# POE_Sheet.net
KiCad netlist of a schematic drawn in Altium Designer
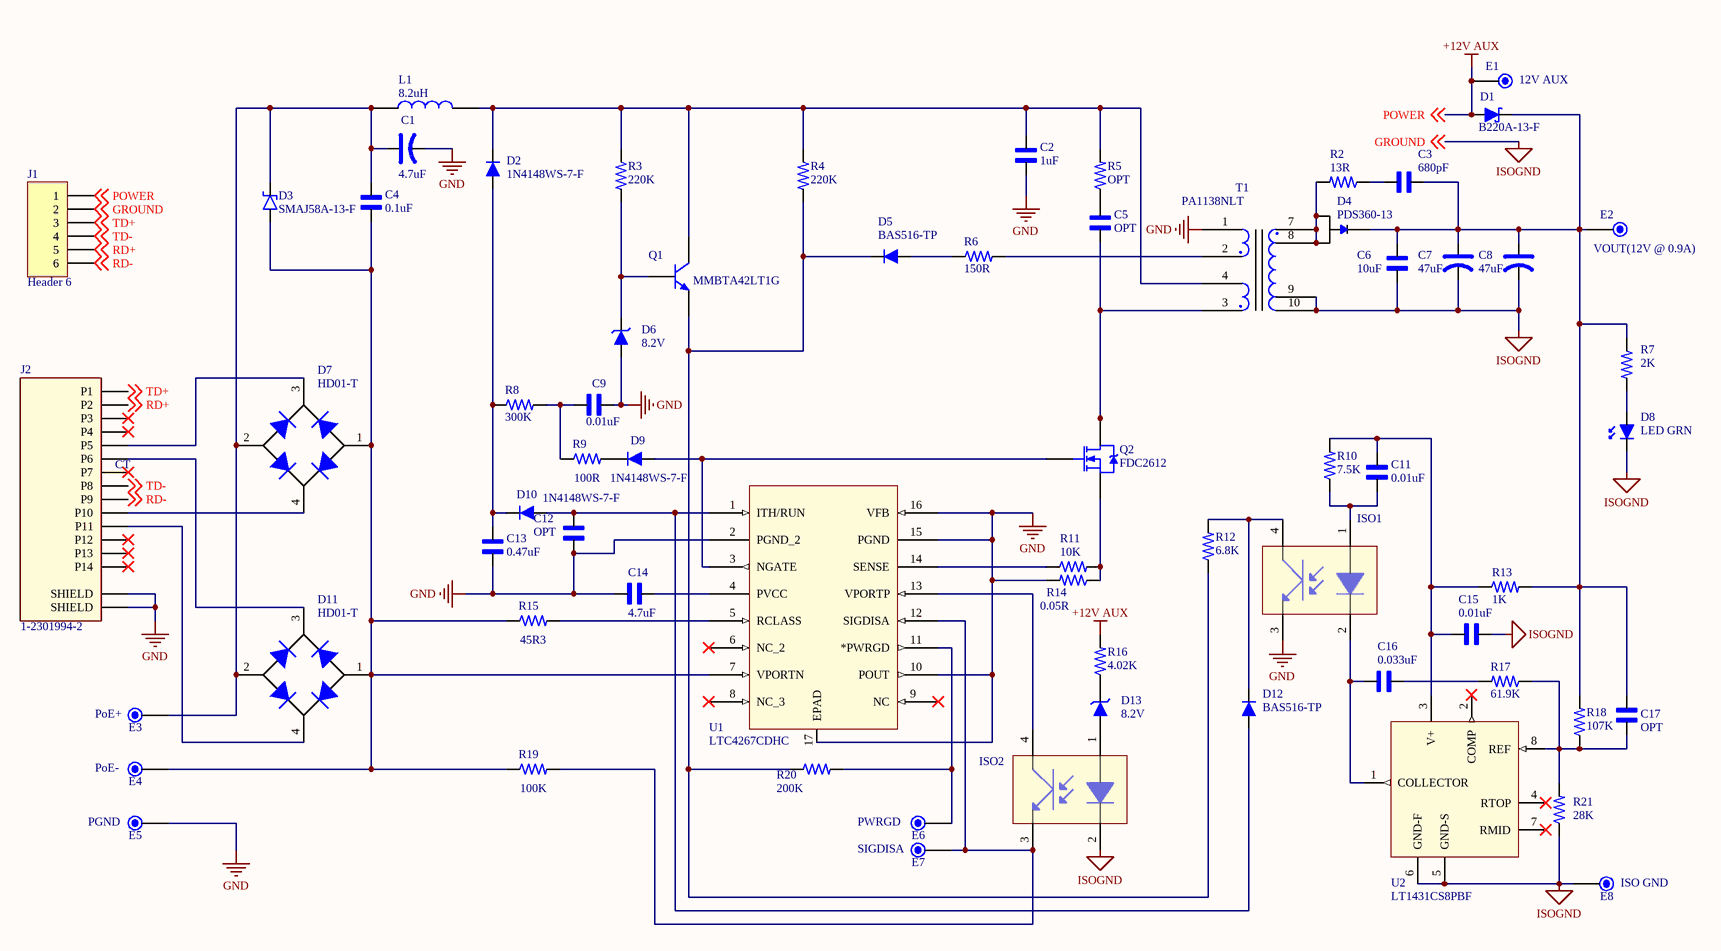
[diagram p0: POE_Sheet.SchDoc]

(export (version "E")
  (design (tool "Eeschema 10.0.6"))
  (components
    (comp (ref "C1")
      (value "4.7uF")
      (footprint "CAPAE5953X52M")
      (description "4.7µF 63V Aluminum Electrolytic Capacitors Radial, Can - SMD 2000 Hrs @ 85°C")
      (fields (field (name "MF") "United Chemi-Con") (field (name "MP") "EMVA630ADA4R7ME55G"))
      (libsource (lib "POE_Schlib") (part "EMVA630ADA4R7ME55G"))
    )
    (comp (ref "C2")
      (value "1uF")
      (footprint "*CAPC1005X55N")
      (description "1µF ±10% 6.3V Ceramic Capacitor X6S 0402 (1005 Metric)")
      (fields (field (name "MF") "Taiyo Yuden") (field (name "MP") "JMK105C6105KV-F"))
      (libsource (lib "POE_Schlib") (part "JMK105C6105KV-F"))
    )
    (comp (ref "C3")
      (value "680pF")
      (footprint "*CAPC1005X55N")
      (description "680pF ±10% 50V Ceramic Capacitor X7R 0402 (1005 Metric)")
      (fields (field (name "MF") "Yageo") (field (name "MP") "CC0402KRX7R9BB681"))
      (libsource (lib "POE_Schlib") (part "CC0402KRX7R9BB681"))
    )
    (comp (ref "C4")
      (value "0.1uF")
      (footprint "*CAPC1005X55N")
      (description "SMD Capacitor X7R(EIA) with Capacitance: 0.10uF Tol. 10%. Rated Voltage: 50Vdc")
      (fields (field (name "MF") "Murata Electronics") (field (name "MP") "GRM155R71H104KE14J"))
      (libsource (lib "POE_Schlib") (part "GRM155R71H104KE14J"))
    )
    (comp (ref "C5") (value "OPT") (footprint "*CAPC1005X55N") (libsource (lib "POE_Schlib") (part "OPT_C")))
    (comp (ref "C6")
      (value "10uF")
      (footprint "*CAPC1005X55N")
      (description "10µF ±20% 4V Ceramic Capacitor X5R 0402 (1005 Metric)")
      (fields (field (name "MF") "Murata Electronics") (field (name "MP") "GRM155R60G106ME44D"))
      (libsource (lib "POE_Schlib") (part "GRM155R60G106ME44D"))
    )
    (comp (ref "C7")
      (value "47uF")
      (footprint "CAPM6032X22N")
      (description "47µF Molded Tantalum Capacitors 16V 2312 (6032 Metric) 350mOhm")
      (fields (field (name "MF") "AVX Corporation") (field (name "MP") "TPSC476K016R0350"))
      (libsource (lib "POE_Schlib") (part "TPSC476K016R0350"))
    )
    (comp (ref "C8")
      (value "47uF")
      (footprint "CAPM6032X22N")
      (description "47µF Molded Tantalum Capacitors 16V 2312 (6032 Metric) 350mOhm")
      (fields (field (name "MF") "AVX Corporation") (field (name "MP") "TPSC476K016R0350"))
      (libsource (lib "POE_Schlib") (part "TPSC476K016R0350"))
    )
    (comp (ref "C9")
      (value "0.01uF")
      (footprint "*CAPC1005X55N")
      (description "0.01uF ±10% 25V Ceramic Capacitor X5R 0402 (1005 Metric)")
      (fields (field (name "MF") "Murata Electronics") (field (name "MP") "GRM155R61E103KA01D"))
      (libsource (lib "POE_Schlib") (part "GRM155R61E103KA01D"))
    )
    (comp (ref "C11")
      (value "0.01uF")
      (footprint "*CAPC1005X55N")
      (description "0.01uF ±10% 25V Ceramic Capacitor X5R 0402 (1005 Metric)")
      (fields (field (name "MF") "Murata Electronics") (field (name "MP") "GRM155R61E103KA01D"))
      (libsource (lib "POE_Schlib") (part "GRM155R61E103KA01D"))
    )
    (comp (ref "C12") (value "OPT") (footprint "*CAPC1005X55N") (libsource (lib "POE_Schlib") (part "OPT_C")))
    (comp (ref "C13")
      (value "0.47uF")
      (footprint "*CAPC1005X55N")
      (description "0.47µF ±10% 50V Ceramic Capacitor X5R 0402 (1005 Metric)")
      (fields (field (name "MF") "Murata Electronics") (field (name "MP") "GRM155R61H474KE11D"))
      (libsource (lib "POE_Schlib") (part "GRM155R61H474KE11D"))
    )
    (comp (ref "C14")
      (value "4.7uF")
      (footprint "*CAPC1005X55N")
      (description "4.7µF ±20% 6.3V Ceramic Capacitor X5R 0402 (1005 Metric)")
      (fields (field (name "MF") "Murata Electronics") (field (name "MP") "GRM155R60J475ME47D"))
      (libsource (lib "POE_Schlib") (part "GRM155R60J475ME47D"))
    )
    (comp (ref "C15")
      (value "0.01uF")
      (footprint "*CAPC1005X55N")
      (description "0.01uF ±10% 25V Ceramic Capacitor X5R 0402 (1005 Metric)")
      (fields (field (name "MF") "Murata Electronics") (field (name "MP") "GRM155R61E103KA01D"))
      (libsource (lib "POE_Schlib") (part "GRM155R61E103KA01D"))
    )
    (comp (ref "C16")
      (value "0.033uF")
      (footprint "*CAPC1005X55N")
      (description "0.033µF -20%, +80% 16V Ceramic Capacitor Y5V (F) 0402 (1005 Metric)")
      (fields (field (name "MF") "Yageo") (field (name "MP") "CC0402ZRY5V7BB333"))
      (libsource (lib "POE_Schlib") (part "CC0402ZRY5V7BB333"))
    )
    (comp (ref "C17") (value "OPT") (footprint "*CAPC1005X55N") (libsource (lib "POE_Schlib") (part "OPT_C")))
    (comp (ref "D1")
      (value "B220A-13-F")
      (footprint "*SMA-DIODE")
      (description "Diode Schottky 20V 2A Surface Mount SMA")
      (fields
        (field (name "DIGI-KEY PART NUMBER") "B220A-FDITR-ND")
        (field (name "MF") "Diodes Incorporated")
      )
      (libsource (lib "POE_Schlib") (part "B220A-13-F"))
    )
    (comp (ref "D2")
      (value "1N4148WS-7-F")
      (footprint "*SOD323_1N4148WS-7-F(Primary)")
      (description "Diode Standard 75V 150mA Surface Mount SOD-323")
      (fields
        (field (name "DIGI-KEY PART NUMBER") "1N4148WS-FDITR-ND")
        (field (name "MF") "Diodes Incorporated")
      )
      (libsource (lib "POE_Schlib") (part "1N4148WS-7-F"))
    )
    (comp (ref "D3")
      (value "SMAJ58A-13-F")
      (footprint "POE_PcbLib:SMAJ")
      (description "93.6V Clamp 4.3A Ipp Tvs Diode Surface Mount SMA")
      (fields (field (name "MF") "Littelfuse Inc."))
      (libsource (lib "POE_Schlib") (part "SMAJ58A-13-F"))
    )
    (comp (ref "D4")
      (value "PDS360-13")
      (footprint "*DIO_PDS360-13")
      (libsource (lib "POE_Schlib") (part "PDS360-13"))
    )
    (comp (ref "D5")
      (value "BAS516-TP")
      (footprint "*SOD323_1N4148WS-7-F(Primary)")
      (description "Diode Standard 75V 250mA (DC) Surface Mount SOD-523")
      (fields
        (field (name "DIGI-KEY PART NUMBER") "BAS516-TPMSTR-ND")
        (field (name "MF") "Micro Commercial Co")
      )
      (libsource (lib "POE_Schlib") (part "BAS516-TP"))
    )
    (comp (ref "D6")
      (value "8.2V")
      (footprint "*SOD323_1N4148WS-7-F(Primary)")
      (description "Zener Diode 8.2V 300mW ±2% Surface Mount SOD-323")
      (fields
        (field (name "DIGI-KEY_PART_NUMBER") "MM3Z8V2ST1GOSTR-ND")
        (field (name "MF") "ON Semiconductor")
      )
      (libsource (lib "POE_Schlib") (part "MM3Z8V2ST1G"))
    )
    (comp (ref "D7")
      (value "HD01-T")
      (footprint "HD01-T")
      (description "Bridge Rectifier Single Phase Standard 100V Surface Mount 4-MiniDIP")
      (fields (field (name "MF") "Diodes Incorporated"))
      (libsource (lib "POE_Schlib") (part "HD01-T"))
    )
    (comp (ref "D8")
      (value "LED GRN")
      (footprint "POE_PcbLib:LED1210")
      (description "Green 525nm LED Indication - Discrete 3.3V 1210 (3225 Metric)")
      (fields (field (name "MP") "APD3224ZGC-F01") (field (name "DIGI-KEY_PART_NUMBER") "754-1089-2-ND"))
      (libsource (lib "POE_Schlib") (part "APD3224ZGC-F01"))
    )
    (comp (ref "D9")
      (value "1N4148WS-7-F")
      (footprint "*SOD323_1N4148WS-7-F(Primary)")
      (description "Diode Standard 75V 150mA Surface Mount SOD-323")
      (fields
        (field (name "DIGI-KEY PART NUMBER") "1N4148WS-FDITR-ND")
        (field (name "MF") "Diodes Incorporated")
      )
      (libsource (lib "POE_Schlib") (part "1N4148WS-7-F"))
    )
    (comp (ref "D10")
      (value "1N4148WS-7-F")
      (footprint "*SOD323_1N4148WS-7-F(Primary)")
      (description "Diode Standard 75V 150mA Surface Mount SOD-323")
      (fields
        (field (name "DIGI-KEY PART NUMBER") "1N4148WS-FDITR-ND")
        (field (name "MF") "Diodes Incorporated")
      )
      (libsource (lib "POE_Schlib") (part "1N4148WS-7-F"))
    )
    (comp (ref "D11")
      (value "HD01-T")
      (footprint "HD01-T")
      (description "Bridge Rectifier Single Phase Standard 100V Surface Mount 4-MiniDIP")
      (fields (field (name "MF") "Diodes Incorporated"))
      (libsource (lib "POE_Schlib") (part "HD01-T"))
    )
    (comp (ref "D12")
      (value "BAS516-TP")
      (footprint "*SOD323_1N4148WS-7-F(Primary)")
      (description "Diode Standard 75V 250mA (DC) Surface Mount SOD-523")
      (fields
        (field (name "DIGI-KEY PART NUMBER") "BAS516-TPMSTR-ND")
        (field (name "MF") "Micro Commercial Co")
      )
      (libsource (lib "POE_Schlib") (part "BAS516-TP"))
    )
    (comp (ref "D13")
      (value "8.2V")
      (footprint "*SOD323_1N4148WS-7-F(Primary)")
      (description "Zener Diode 8.2V 300mW ±2% Surface Mount SOD-323")
      (fields
        (field (name "DIGI-KEY_PART_NUMBER") "MM3Z8V2ST1GOSTR-ND")
        (field (name "MF") "ON Semiconductor")
      )
      (libsource (lib "POE_Schlib") (part "MM3Z8V2ST1G"))
    )
    (comp (ref "E1") (value "12V AUX") (footprint "E_PAD") (libsource (lib "POE_Schlib") (part "E_PAD")))
    (comp (ref "E2")
      (value "VOUT(12V @ 0.9A)")
      (footprint "E_PAD")
      (libsource (lib "POE_Schlib") (part "E_PAD"))
    )
    (comp (ref "E3") (value "PoE+") (footprint "E_PAD") (libsource (lib "POE_Schlib") (part "E_PAD")))
    (comp (ref "E4") (value "PoE-") (footprint "E_PAD") (libsource (lib "POE_Schlib") (part "E_PAD")))
    (comp (ref "E5") (value "PGND") (footprint "E_PAD") (libsource (lib "POE_Schlib") (part "E_PAD")))
    (comp (ref "E6") (value "PWRGD") (footprint "E_PAD") (libsource (lib "POE_Schlib") (part "E_PAD")))
    (comp (ref "E7") (value "SIGDISA") (footprint "E_PAD") (libsource (lib "POE_Schlib") (part "E_PAD")))
    (comp (ref "E8") (value "ISO GND") (footprint "E_PAD") (libsource (lib "POE_Schlib") (part "E_PAD")))
    (comp (ref "ISO1")
      (value "PS2913-1-K-A")
      (footprint "SOic254P1016X440-4N")
      (description "Optoisolator Transistor Output 2500Vrms 1 Channel 4-Mini-Flat")
      (fields (field (name "DIGI-KEY_PART_NUMBER") "PS2913-1-K-A-ND") (field (name "MF") "CEL"))
      (libsource (lib "POE_Schlib") (part "PS2913-1-K-A"))
    )
    (comp (ref "ISO2")
      (value "PS2913-1-K-A")
      (footprint "SOic254P1016X440-4N")
      (description "Optoisolator Transistor Output 2500Vrms 1 Channel 4-Mini-Flat")
      (fields (field (name "DIGI-KEY_PART_NUMBER") "PS2913-1-K-A-ND") (field (name "MF") "CEL"))
      (libsource (lib "POE_Schlib") (part "PS2913-1-K-A"))
    )
    (comp (ref "J1")
      (value "Header 6")
      (footprint "HDR1X6")
      (description "Header, 6-Pin")
      (fields (field (name "PUBLISHER") "Altium Limited"))
      (libsource (lib "Miscellaneous Connectors") (part "Header 6"))
    )
    (comp (ref "J2")
      (value "1-2301994-2")
      (footprint "*TE_1-2301994-2_1-2301994-2(Primary)")
      (libsource (lib "POE_Schlib") (part "1-2301994-2"))
    )
    (comp (ref "L1")
      (value "8.2uH")
      (footprint "INDP6866X23N")
      (description "8.2µH Shielded Molded Inductor 4A 68mOhm Max Nonstandard")
      (fields (field (name "MF") "Vishay Dale") (field (name "MP") "IHLP2525CZER8R2M01"))
      (libsource (lib "POE_Schlib") (part "IHLP2525CZER8R2M01"))
    )
    (comp (ref "Q1")
      (value "MMBTA42LT1G")
      (footprint "SOT-23-3(TO-236)")
      (description "Bipolar (BJT) Transistor NPN 300V 500mA 50MHz 225mW Surface Mount SOT-23-3 (TO-236)")
      (fields
        (field (name "MF") "ON Semiconductor")
        (field (name "DIGI-KEY_PART_NUMBER") "MMBTA42LT1GOSTR-ND")
      )
      (libsource (lib "POE_Schlib") (part "MMBTA42LT1G"))
    )
    (comp (ref "Q2")
      (value "FDC2612")
      (footprint "*SOT95P280X100-6N")
      (description "N-Channel 200V 1.1A (Ta) 1.6W (Ta) Surface Mount SuperSOT™-6")
      (fields (field (name "DIGI-KEY PART NUMBER") "FDC2612TR-ND") (field (name "MF") "ON Semiconductor"))
      (libsource (lib "POE_Schlib") (part "FDC2612"))
    )
    (comp (ref "R2")
      (value "13R")
      (footprint "POE_PcbLib:RESC1005X40N")
      (description "13 Ohms ±1% 0.063W, 1/16W Chip Resistor 0402 (1005 Metric) Moisture Resistant Thick Film")
      (fields (field (name "MP") "RC0402FR-0713RL") (field (name "DIGI-KEY_PART_NUMBER") "YAG2977TR-ND"))
      (libsource (lib "POE_Schlib") (part "RC0402FR-0713RL"))
    )
    (comp (ref "R3")
      (value "220K")
      (footprint "POE_PcbLib:RESC1005X40N")
      (fields
        (field (name "MP") "CRGCQ0402F220K")
        (field (name "DIGI-KEY_PART_NUMBER") "A129655TR-ND")
        (field (name "MF") "TE Connectivity Passive Product")
      )
      (libsource (lib "POE_Schlib") (part "CRGCQ0402F220K"))
    )
    (comp (ref "R4")
      (value "220K")
      (footprint "POE_PcbLib:RESC1005X40N")
      (fields
        (field (name "MP") "CRGCQ0402F220K")
        (field (name "DIGI-KEY_PART_NUMBER") "A129655TR-ND")
        (field (name "MF") "TE Connectivity Passive Product")
      )
      (libsource (lib "POE_Schlib") (part "CRGCQ0402F220K"))
    )
    (comp (ref "R5")
      (value "OPT")
      (footprint "POE_PcbLib:RESC1005X40N")
      (libsource (lib "POE_Schlib") (part "OPT_R"))
    )
    (comp (ref "R6")
      (value "150R")
      (footprint "POE_PcbLib:RESC1005X40N")
      (description "150 Ohms ±1% 0.063W, 1/16W Chip Resistor 0402 (1005 Metric) Moisture Resistant Thick Film")
      (fields (field (name "MP") "RC0402FR-07150RL") (field (name "DIGI-KEY_PART_NUMBER") "311-150LRTR-ND"))
      (libsource (lib "POE_Schlib") (part "RC0402FR-07150RL"))
    )
    (comp (ref "R7")
      (value "2K")
      (footprint "POE_PcbLib:RESC1005X40N")
      (description "2 kOhms ±1% 0.063W, 1/16W Chip Resistor 0402 (1005 Metric) Moisture Resistant Thick Film")
      (fields (field (name "MP") "RC0402FR-072KL") (field (name "DIGI-KEY_PART_NUMBER") "311-2KLRTR-ND"))
      (libsource (lib "POE_Schlib") (part "RC0402FR-072KL"))
    )
    (comp (ref "R8")
      (value "300K")
      (footprint "POE_PcbLib:RESC1005X40N")
      (description "300 kOhms ±0.1% 0.063W, 1/16W Chip Resistor 0402 (1005 Metric) Moisture Resistant Metal Film")
      (fields
        (field (name "MP") "RN73R1ETTP3003B25")
        (field (name "DIGI-KEY_PART_NUMBER") "2019-RN73R1ETTP3003B25TR-ND")
      )
      (libsource (lib "POE_Schlib") (part "RN73R1ETTP3003B25"))
    )
    (comp (ref "R9")
      (value "100R")
      (footprint "POE_PcbLib:RESC1005X40N")
      (description "100 Ohms ±1% 0.063W, 1/16W Chip Resistor 0402 (1005 Metric) Moisture Resistant Thick Film")
      (fields (field (name "MP") "RC0402FR-07100RL") (field (name "DIGI-KEY_PART_NUMBER") "311-100LRTR-ND"))
      (libsource (lib "POE_Schlib") (part "RC0402FR-07100RL"))
    )
    (comp (ref "R10")
      (value "7.5K")
      (footprint "POE_PcbLib:RESC1005X40N")
      (description "7.5 kOhms ±0.1% 0.063W, 1/16W Chip Resistor 0402 (1005 Metric) Automotive AEC-Q200 Thin Film")
      (fields (field (name "MP") "ERA-2AEB752X") (field (name "DIGI-KEY_PART_NUMBER") "P7.5KDCTR-ND"))
      (libsource (lib "POE_Schlib") (part "ERA-2AEB752X"))
    )
    (comp (ref "R11")
      (value "10K")
      (footprint "POE_PcbLib:RESC1005X40N")
      (description "10 kOhms ±1% 0.063W, 1/16W Chip Resistor 0402 (1005 Metric) Moisture Resistant Thick Film")
      (fields (field (name "MP") "RC0402FR-0710KL") (field (name "DIGI-KEY_PART_NUMBER") "311-10.0KLRTR-ND"))
      (libsource (lib "POE_Schlib") (part "RC0402FR-0710KL"))
    )
    (comp (ref "R12")
      (value "6.8K")
      (footprint "POE_PcbLib:RESC1005X40N")
      (description "6.8 kOhms ±0.5% 0.063W, 1/16W Chip Resistor 0402 (1005 Metric) Automotive AEC-Q200 Thin Film")
      (fields (field (name "MP") "ERA-2AED682X") (field (name "DIGI-KEY_PART_NUMBER") "P6.8KDETR-ND"))
      (libsource (lib "POE_Schlib") (part "ERA-2AED682X"))
    )
    (comp (ref "R13")
      (value "1K")
      (footprint "POE_PcbLib:RESC1005X40N")
      (description "1 kOhms ±1% 0.063W, 1/16W Chip Resistor 0402 (1005 Metric) Moisture Resistant Thick Film")
      (fields (field (name "MP") "RC0402FR-071KL") (field (name "DIGI-KEY_PART_NUMBER") "311-1.00KLRTR-ND"))
      (libsource (lib "POE_Schlib") (part "RC0402FR-071KL"))
    )
    (comp (ref "R14")
      (value "0.05R")
      (footprint "POE_PcbLib:RESC1005X40N")
      (fields
        (field (name "MP") "ERJ-2BWFR050X")
        (field (name "DIGI-KEY_PART_NUMBER") "P17367TR-ND")
        (field (name "MF") "Panasonic Electronic Components")
      )
      (libsource (lib "POE_Schlib") (part "ERJ-2BWFR050X"))
    )
    (comp (ref "R15")
      (value "45R3")
      (footprint "POE_PcbLib:RESC1005X40N")
      (description "Fixed Resistor RP 1E 0.1W 45R3 0.1% 25PPM 5K RL")
      (fields (field (name "MP") "RP73PF1E45R3BTD") (field (name "DIGI-KEY_PART_NUMBER") "A127190TR-ND"))
      (libsource (lib "POE_Schlib") (part "RP73PF1E45R3BTD"))
    )
    (comp (ref "R16")
      (value "4.02K")
      (footprint "POE_PcbLib:RESC1005X40N")
      (description "4.02 kOhms ±0.1% 0.063W, 1/16W Chip Resistor 0402 (1005 Metric) Automotive AEC-Q200 Thin Film")
      (fields (field (name "MP") "ERA-2AEB4021X") (field (name "DIGI-KEY_PART_NUMBER") "P4.02KDCTR-ND"))
      (libsource (lib "POE_Schlib") (part "ERA-2AEB4021X"))
    )
    (comp (ref "R17")
      (value "61.9K")
      (footprint "POE_PcbLib:RESC1005X40N")
      (description "61.9 kOhms ±1% 0.063W, 1/16W Chip Resistor 0402 (1005 Metric) Automotive AEC-Q200 Thick Film")
      (fields
        (field (name "MP") "RMCF0402FT61K9")
        (field (name "DIGI-KEY_PART_NUMBER") "RMCF0402FT61K9TR-ND")
      )
      (libsource (lib "POE_Schlib") (part "RMCF0402FT61K9"))
    )
    (comp (ref "R18")
      (value "107K")
      (footprint "POE_PcbLib:RESC1005X40N")
      (description "107 kOhms ±0.1% 0.1W, 1/10W Chip Resistor 0402 (1005 Metric) Thin Film")
      (fields (field (name "MP") "RP73PF1E107KBTD") (field (name "DIGI-KEY_PART_NUMBER") "A127514TR-ND"))
      (libsource (lib "POE_Schlib") (part "RP73PF1E107KBTD"))
    )
    (comp (ref "R19")
      (value "100K")
      (footprint "POE_PcbLib:RESC1005X40N")
      (description "100 kOhms Â±0.1% 0.063W, 1/16W Chip Resistor 0402 _1005 Metric_ Automotive AEC-Q200 Thin Film")
      (fields (field (name "MP") "ERA-2AEB104X") (field (name "DIGI-KEY_PART_NUMBER") "P100KDCCT-ND"))
      (libsource (lib "POE_Schlib") (part "ERA-2AEB104X"))
    )
    (comp (ref "R20")
      (value "200K")
      (footprint "POE_PcbLib:RESC1005X40N")
      (description "200 kOhms ±0.1% 0.063W, 1/16W Chip Resistor 0402 (1005 Metric) Thin Film")
      (fields (field (name "MP") "CPF0402B200KE") (field (name "DIGI-KEY_PART_NUMBER") "A119933TR-ND"))
      (libsource (lib "POE_Schlib") (part "CPF0402B200KE"))
    )
    (comp (ref "R21")
      (value "28K")
      (footprint "POE_PcbLib:RESC1005X40N")
      (description "28 kOhms ±0.1% 0.063W, 1/16W Chip Resistor 0402 (1005 Metric) Automotive AEC-Q200 Thin Film")
      (fields (field (name "MP") "ERA-2AEB2802X") (field (name "DIGI-KEY_PART_NUMBER") "P28KDCTR-ND"))
      (libsource (lib "POE_Schlib") (part "ERA-2AEB2802X"))
    )
    (comp (ref "T1")
      (value "PA1138NLT")
      (footprint "POE_PcbLib:EP13T")
      (description "127µH Isolation and Data Interface (Encapsulated) Pulse Transformer 1:0.292:0.208 Surface Mount")
      (fields
        (field (name "DIGI-KEY_PART_NUMBER") "553-1984-1-ND")
        (field (name "MF") "Pulse Electronics Power")
      )
      (libsource (lib "POE_Schlib") (part "PA1138NLT"))
    )
    (comp (ref "U1")
      (value "LTC4267CDHC")
      (footprint "POE_PcbLib:DFN-16_DHC")
      (fields (field (name "MF") "Analog Devices / Linear Technology"))
      (libsource (lib "POE_Schlib") (part "LTC4267CDHC"))
    )
    (comp (ref "U2")
      (value "LT1431CS8PBF")
      (footprint "*SO-8_S")
      (description "Shunt Voltage Reference IC 36V ±0.4% 8-SOIC")
      (fields
        (field (name "DIGI-KEY PART NUMBER") "LT1431CS8#PBF-ND")
        (field (name "MF") "Linear Technology/Analog Devices")
      )
      (libsource (lib "POE_Schlib") (part "LT1431CS8PBF"))
    )
  )
  (nets
    (net (code "1") (name "+12V AUX") (class "Default")
      (node (ref "D1") (pin "1") (pinfunction "A_1") (pintype "passive"))
      (node (ref "E1") (pin "1") (pinfunction "1_1") (pintype "passive"))
      (node (ref "J1") (pin "1") (pinfunction "1_1") (pintype "passive"))
      (node (ref "R16") (pin "2") (pinfunction "2_2") (pintype "passive"))
    )
    (net (code "2") (name "GND") (class "Default")
      (node (ref "C1") (pin "2") (pinfunction "2_2") (pintype "passive"))
      (node (ref "C12") (pin "2") (pinfunction "2_2") (pintype "passive"))
      (node (ref "C13") (pin "1") (pinfunction "1_1") (pintype "passive"))
      (node (ref "C14") (pin "1") (pinfunction "1_1") (pintype "passive"))
      (node (ref "C2") (pin "2") (pinfunction "2_2") (pintype "passive"))
      (node (ref "C9") (pin "1") (pinfunction "1_1") (pintype "passive"))
      (node (ref "D6") (pin "A") (pinfunction "A_A") (pintype "passive"))
      (node (ref "E5") (pin "1") (pinfunction "1_1") (pintype "passive"))
      (node (ref "ISO1") (pin "3") (pinfunction "3_3") (pintype "passive"))
      (node (ref "J2") (pin "SH1") (pinfunction "SHIELD_SH1") (pintype "passive"))
      (node (ref "J2") (pin "SH2") (pinfunction "SHIELD_SH2") (pintype "passive"))
      (node (ref "R14") (pin "2") (pinfunction "2_2") (pintype "passive"))
      (node (ref "T1") (pin "1") (pinfunction "1_1") (pintype "passive"))
      (node (ref "U1") (pin "10") (pinfunction "POUT_10") (pintype "output"))
      (node (ref "U1") (pin "15") (pinfunction "PGND_15") (pintype "power_in"))
      (node (ref "U1") (pin "16") (pinfunction "VFB_16") (pintype "input"))
      (node (ref "U1") (pin "17") (pinfunction "EPAD_17") (pintype "passive"))
      (node (ref "U1") (pin "2") (pinfunction "PGND_2_2") (pintype "power_in"))
    )
    (net (code "3") (name "GROUND") (class "Default")
      (node (ref "C15") (pin "2") (pinfunction "2_2") (pintype "passive"))
      (node (ref "C6") (pin "1") (pinfunction "1_1") (pintype "passive"))
      (node (ref "C7") (pin "2") (pinfunction "2_2") (pintype "passive"))
      (node (ref "C8") (pin "2") (pinfunction "2_2") (pintype "passive"))
      (node (ref "D8") (pin "K") (pinfunction "K_K") (pintype "passive"))
      (node (ref "E8") (pin "1") (pinfunction "1_1") (pintype "passive"))
      (node (ref "ISO2") (pin "2") (pinfunction "2_2") (pintype "passive"))
      (node (ref "J1") (pin "2") (pinfunction "2_2") (pintype "passive"))
      (node (ref "R21") (pin "1") (pinfunction "1_1") (pintype "passive"))
      (node (ref "T1") (pin "10") (pinfunction "10_10") (pintype "passive"))
      (node (ref "T1") (pin "9") (pinfunction "9_9") (pintype "passive"))
      (node (ref "U2") (pin "5") (pinfunction "GND-S_5") (pintype "power_in"))
      (node (ref "U2") (pin "6") (pinfunction "GND-F_6") (pintype "power_in"))
    )
    (net (code "4") (name "Net-(C1-Pad1)") (class "Default")
      (node (ref "C1") (pin "1") (pinfunction "1_1") (pintype "passive"))
      (node (ref "C4") (pin "1") (pinfunction "1_1") (pintype "passive"))
      (node (ref "D11") (pin "2") (pinfunction "2_2") (pintype "passive"))
      (node (ref "D3") (pin "A") (pinfunction "A_A") (pintype "passive"))
      (node (ref "D7") (pin "2") (pinfunction "2_2") (pintype "passive"))
      (node (ref "E3") (pin "1") (pinfunction "1_1") (pintype "passive"))
      (node (ref "L1") (pin "1") (pinfunction "1_1") (pintype "passive"))
    )
    (net (code "5") (name "Net-(C3-Pad1)") (class "Default")
      (node (ref "C3") (pin "1") (pinfunction "1_1") (pintype "passive"))
      (node (ref "R2") (pin "1") (pinfunction "1_1") (pintype "passive"))
    )
    (net (code "6") (name "Net-(C5-Pad1)") (class "Default")
      (node (ref "C5") (pin "1") (pinfunction "1_1") (pintype "passive"))
      (node (ref "R5") (pin "1") (pinfunction "1_1") (pintype "passive"))
    )
    (net (code "7") (name "Net-(C5-Pad2)") (class "Default")
      (node (ref "C5") (pin "2") (pinfunction "2_2") (pintype "passive"))
      (node (ref "Q2") (pin "1") (pinfunction "D_1") (pintype "passive"))
      (node (ref "Q2") (pin "2") (pinfunction "D_2") (pintype "passive"))
      (node (ref "Q2") (pin "5") (pinfunction "D_5") (pintype "passive"))
      (node (ref "Q2") (pin "6") (pinfunction "D_6") (pintype "passive"))
      (node (ref "T1") (pin "3") (pinfunction "3_3") (pintype "passive"))
    )
    (net (code "8") (name "Net-(C9-Pad2)") (class "Default")
      (node (ref "C9") (pin "2") (pinfunction "2_2") (pintype "passive"))
      (node (ref "R8") (pin "2") (pinfunction "2_2") (pintype "passive"))
      (node (ref "R9") (pin "1") (pinfunction "1_1") (pintype "passive"))
    )
    (net (code "9") (name "Net-(C11-Pad1)") (class "Default")
      (node (ref "C11") (pin "1") (pinfunction "1_1") (pintype "passive"))
      (node (ref "ISO1") (pin "1") (pinfunction "1_1") (pintype "passive"))
      (node (ref "R10") (pin "1") (pinfunction "1_1") (pintype "passive"))
    )
    (net (code "10") (name "Net-(C13-Pad2)") (class "Default")
      (node (ref "C13") (pin "2") (pinfunction "2_2") (pintype "passive"))
      (node (ref "D10") (pin "C") (pinfunction "C_C") (pintype "passive"))
      (node (ref "D2") (pin "A") (pinfunction "A_A") (pintype "passive"))
      (node (ref "R8") (pin "1") (pinfunction "1_1") (pintype "passive"))
    )
    (net (code "11") (name "Net-(C16-Pad2)") (class "Default")
      (node (ref "C16") (pin "2") (pinfunction "2_2") (pintype "passive"))
      (node (ref "R17") (pin "2") (pinfunction "2_2") (pintype "passive"))
    )
    (net (code "12") (name "Net-(D1-C)") (class "Default")
      (node (ref "C17") (pin "2") (pinfunction "2_2") (pintype "passive"))
      (node (ref "C3") (pin "2") (pinfunction "2_2") (pintype "passive"))
      (node (ref "C6") (pin "2") (pinfunction "2_2") (pintype "passive"))
      (node (ref "C7") (pin "1") (pinfunction "1_1") (pintype "passive"))
      (node (ref "C8") (pin "1") (pinfunction "1_1") (pintype "passive"))
      (node (ref "D1") (pin "2") (pinfunction "C_2") (pintype "passive"))
      (node (ref "D4") (pin "3") (pinfunction "HEATSINK_CATHODE_3") (pintype "passive"))
      (node (ref "E2") (pin "1") (pinfunction "1_1") (pintype "passive"))
      (node (ref "R13") (pin "2") (pinfunction "2_2") (pintype "passive"))
      (node (ref "R18") (pin "2") (pinfunction "2_2") (pintype "passive"))
      (node (ref "R7") (pin "1") (pinfunction "1_1") (pintype "passive"))
    )
    (net (code "13") (name "Net-(D4-LEFT_PIN_ANODE)") (class "Default")
      (node (ref "D4") (pin "1") (pinfunction "LEFT_PIN_ANODE_1") (pintype "passive"))
      (node (ref "D4") (pin "2") (pinfunction "RIGHT_PIN_ANODE_2") (pintype "passive"))
      (node (ref "R2") (pin "2") (pinfunction "2_2") (pintype "passive"))
      (node (ref "T1") (pin "7") (pinfunction "7_7") (pintype "passive"))
      (node (ref "T1") (pin "8") (pinfunction "8_8") (pintype "passive"))
    )
    (net (code "14") (name "Net-(D5-PadA)") (class "Default")
      (node (ref "D5") (pin "A") (pinfunction "A_A") (pintype "passive"))
      (node (ref "R6") (pin "1") (pinfunction "1_1") (pintype "passive"))
    )
    (net (code "15") (name "Net-(D7-Pad3)") (class "Default")
      (node (ref "D7") (pin "3") (pinfunction "3_3") (pintype "passive"))
      (node (ref "J2") (pin "P5") (pinfunction "P5_P5") (pintype "passive"))
    )
    (net (code "16") (name "Net-(D7-Pad4)") (class "Default")
      (node (ref "D7") (pin "4") (pinfunction "4_4") (pintype "passive"))
      (node (ref "J2") (pin "P10") (pinfunction "P10_P10") (pintype "passive"))
    )
    (net (code "17") (name "Net-(D8-PadA)") (class "Default")
      (node (ref "D8") (pin "A") (pinfunction "A_A") (pintype "passive"))
      (node (ref "R7") (pin "2") (pinfunction "2_2") (pintype "passive"))
    )
    (net (code "18") (name "Net-(D9-PadC)") (class "Default")
      (node (ref "D9") (pin "C") (pinfunction "C_C") (pintype "passive"))
      (node (ref "R9") (pin "2") (pinfunction "2_2") (pintype "passive"))
    )
    (net (code "19") (name "Net-(D11-Pad3)") (class "Default")
      (node (ref "D11") (pin "3") (pinfunction "3_3") (pintype "passive"))
      (node (ref "J2") (pin "P6") (pinfunction "P6_P6") (pintype "passive"))
    )
    (net (code "20") (name "Net-(D11-Pad4)") (class "Default")
      (node (ref "D11") (pin "4") (pinfunction "4_4") (pintype "passive"))
      (node (ref "J2") (pin "P11") (pinfunction "P11_P11") (pintype "passive"))
    )
    (net (code "21") (name "Net-(D12-PadC)") (class "Default")
      (node (ref "D12") (pin "C") (pinfunction "C_C") (pintype "passive"))
      (node (ref "ISO1") (pin "4") (pinfunction "4_4") (pintype "passive"))
      (node (ref "R12") (pin "2") (pinfunction "2_2") (pintype "passive"))
    )
    (net (code "22") (name "Net-(D13-PadA)") (class "Default")
      (node (ref "D13") (pin "A") (pinfunction "A_A") (pintype "passive"))
      (node (ref "ISO2") (pin "1") (pinfunction "1_1") (pintype "passive"))
    )
    (net (code "23") (name "Net-(D13-PadC)") (class "Default")
      (node (ref "D13") (pin "C") (pinfunction "C_C") (pintype "passive"))
      (node (ref "R16") (pin "1") (pinfunction "1_1") (pintype "passive"))
    )
    (net (code "24") (name "Net-(Q1-B)") (class "Default")
      (node (ref "D6") (pin "C") (pinfunction "C_C") (pintype "passive"))
      (node (ref "Q1") (pin "2") (pinfunction "B_2") (pintype "passive"))
      (node (ref "R3") (pin "2") (pinfunction "2_2") (pintype "passive"))
    )
    (net (code "25") (name "Net-(Q1-C)") (class "Default")
      (node (ref "C2") (pin "1") (pinfunction "1_1") (pintype "passive"))
      (node (ref "D2") (pin "C") (pinfunction "C_C") (pintype "passive"))
      (node (ref "L1") (pin "2") (pinfunction "2_2") (pintype "passive"))
      (node (ref "Q1") (pin "1") (pinfunction "C_1") (pintype "passive"))
      (node (ref "R3") (pin "1") (pinfunction "1_1") (pintype "passive"))
      (node (ref "R4") (pin "1") (pinfunction "1_1") (pintype "passive"))
      (node (ref "R5") (pin "2") (pinfunction "2_2") (pintype "passive"))
      (node (ref "T1") (pin "4") (pinfunction "4_4") (pintype "passive"))
    )
    (net (code "26") (name "Net-(Q1-E)") (class "Default")
      (node (ref "D5") (pin "C") (pinfunction "C_C") (pintype "passive"))
      (node (ref "Q1") (pin "3") (pinfunction "E_3") (pintype "passive"))
      (node (ref "R12") (pin "1") (pinfunction "1_1") (pintype "passive"))
      (node (ref "R20") (pin "1") (pinfunction "1_1") (pintype "passive"))
      (node (ref "R4") (pin "2") (pinfunction "2_2") (pintype "passive"))
    )
    (net (code "27") (name "Net-(Q2-G)") (class "Default")
      (node (ref "D9") (pin "A") (pinfunction "A_A") (pintype "passive"))
      (node (ref "Q2") (pin "3") (pinfunction "G_3") (pintype "passive"))
      (node (ref "U1") (pin "3") (pinfunction "NGATE_3") (pintype "output"))
    )
    (net (code "28") (name "Net-(Q2-S)") (class "Default")
      (node (ref "Q2") (pin "4") (pinfunction "S_4") (pintype "passive"))
      (node (ref "R11") (pin "2") (pinfunction "2_2") (pintype "passive"))
      (node (ref "R14") (pin "1") (pinfunction "1_1") (pintype "passive"))
    )
    (net (code "29") (name "Net-(R6-Pad2)") (class "Default")
      (node (ref "R6") (pin "2") (pinfunction "2_2") (pintype "passive"))
      (node (ref "T1") (pin "2") (pinfunction "2_2") (pintype "passive"))
    )
    (net (code "30") (name "Net-(U1-*PWRGD)") (class "Default")
      (node (ref "E6") (pin "1") (pinfunction "1_1") (pintype "passive"))
      (node (ref "R20") (pin "2") (pinfunction "2_2") (pintype "passive"))
      (node (ref "U1") (pin "11") (pinfunction "*PWRGD_11") (pintype "output"))
    )
    (net (code "31") (name "Net-(U1-ITH{slash}RUN)") (class "Default")
      (node (ref "C12") (pin "1") (pinfunction "1_1") (pintype "passive"))
      (node (ref "D10") (pin "A") (pinfunction "A_A") (pintype "passive"))
      (node (ref "D12") (pin "A") (pinfunction "A_A") (pintype "passive"))
      (node (ref "U1") (pin "1") (pinfunction "ITH/RUN_1") (pintype "input"))
    )
    (net (code "32") (name "Net-(U1-PVCC)") (class "Default")
      (node (ref "C14") (pin "2") (pinfunction "2_2") (pintype "passive"))
      (node (ref "U1") (pin "4") (pinfunction "PVCC_4") (pintype "power_in"))
    )
    (net (code "33") (name "Net-(U1-RCLASS)") (class "Default")
      (node (ref "R15") (pin "2") (pinfunction "2_2") (pintype "passive"))
      (node (ref "U1") (pin "5") (pinfunction "RCLASS_5") (pintype "input"))
    )
    (net (code "34") (name "Net-(U1-SENSE)") (class "Default")
      (node (ref "R11") (pin "1") (pinfunction "1_1") (pintype "passive"))
      (node (ref "U1") (pin "14") (pinfunction "SENSE_14") (pintype "passive"))
    )
    (net (code "35") (name "Net-(U1-SIGDISA)") (class "Default")
      (node (ref "E7") (pin "1") (pinfunction "1_1") (pintype "passive"))
      (node (ref "ISO2") (pin "3") (pinfunction "3_3") (pintype "passive"))
      (node (ref "R19") (pin "2") (pinfunction "2_2") (pintype "passive"))
      (node (ref "U1") (pin "12") (pinfunction "SIGDISA_12") (pintype "input"))
    )
    (net (code "36") (name "Net-(U1-VPORTN)") (class "Default")
      (node (ref "C4") (pin "2") (pinfunction "2_2") (pintype "passive"))
      (node (ref "D11") (pin "1") (pinfunction "1_1") (pintype "passive"))
      (node (ref "D3") (pin "K") (pinfunction "K_K") (pintype "passive"))
      (node (ref "D7") (pin "1") (pinfunction "1_1") (pintype "passive"))
      (node (ref "E4") (pin "1") (pinfunction "1_1") (pintype "passive"))
      (node (ref "R15") (pin "1") (pinfunction "1_1") (pintype "passive"))
      (node (ref "R19") (pin "1") (pinfunction "1_1") (pintype "passive"))
      (node (ref "U1") (pin "7") (pinfunction "VPORTN_7") (pintype "input"))
    )
    (net (code "37") (name "Net-(U1-VPORTP)") (class "Default")
      (node (ref "ISO2") (pin "4") (pinfunction "4_4") (pintype "passive"))
      (node (ref "U1") (pin "13") (pinfunction "VPORTP_13") (pintype "input"))
    )
    (net (code "38") (name "Net-(U2-COLLECTOR)") (class "Default")
      (node (ref "C16") (pin "1") (pinfunction "1_1") (pintype "passive"))
      (node (ref "ISO1") (pin "2") (pinfunction "2_2") (pintype "passive"))
      (node (ref "U2") (pin "1") (pinfunction "COLLECTOR_1") (pintype "output"))
    )
    (net (code "39") (name "Net-(U2-REF)") (class "Default")
      (node (ref "C17") (pin "1") (pinfunction "1_1") (pintype "passive"))
      (node (ref "R17") (pin "1") (pinfunction "1_1") (pintype "passive"))
      (node (ref "R18") (pin "1") (pinfunction "1_1") (pintype "passive"))
      (node (ref "R21") (pin "2") (pinfunction "2_2") (pintype "passive"))
      (node (ref "U2") (pin "8") (pinfunction "REF_8") (pintype "input"))
    )
    (net (code "40") (name "Net-(U2-V+)") (class "Default")
      (node (ref "C11") (pin "2") (pinfunction "2_2") (pintype "passive"))
      (node (ref "C15") (pin "1") (pinfunction "1_1") (pintype "passive"))
      (node (ref "R10") (pin "2") (pinfunction "2_2") (pintype "passive"))
      (node (ref "R13") (pin "1") (pinfunction "1_1") (pintype "passive"))
      (node (ref "U2") (pin "3") (pinfunction "V+_3") (pintype "power_in"))
    )
    (net (code "41") (name "RD+") (class "Default")
      (node (ref "J1") (pin "5") (pinfunction "5_5") (pintype "passive"))
      (node (ref "J2") (pin "P2") (pinfunction "P2_P2") (pintype "passive"))
    )
    (net (code "42") (name "RD-") (class "Default")
      (node (ref "J1") (pin "6") (pinfunction "6_6") (pintype "passive"))
      (node (ref "J2") (pin "P9") (pinfunction "P9_P9") (pintype "passive"))
    )
    (net (code "43") (name "TD+") (class "Default")
      (node (ref "J1") (pin "3") (pinfunction "3_3") (pintype "passive"))
      (node (ref "J2") (pin "P1") (pinfunction "P1_P1") (pintype "passive"))
    )
    (net (code "44") (name "TD-") (class "Default")
      (node (ref "J1") (pin "4") (pinfunction "4_4") (pintype "passive"))
      (node (ref "J2") (pin "P8") (pinfunction "P8_P8") (pintype "passive"))
    )
    (net (code "45") (name "unconnected-(J2-PadP3)") (class "Default")
      (node (ref "J2") (pin "P3") (pinfunction "P3_P3") (pintype "passive+no_connect"))
    )
    (net (code "46") (name "unconnected-(J2-PadP4)") (class "Default")
      (node (ref "J2") (pin "P4") (pinfunction "P4_P4") (pintype "passive+no_connect"))
    )
    (net (code "47") (name "unconnected-(J2-PadP7)") (class "Default")
      (node (ref "J2") (pin "P7") (pinfunction "P7_P7") (pintype "passive+no_connect"))
    )
    (net (code "48") (name "unconnected-(J2-PadP12)") (class "Default")
      (node (ref "J2") (pin "P12") (pinfunction "P12_P12") (pintype "passive+no_connect"))
    )
    (net (code "49") (name "unconnected-(J2-PadP13)") (class "Default")
      (node (ref "J2") (pin "P13") (pinfunction "P13_P13") (pintype "passive+no_connect"))
    )
    (net (code "50") (name "unconnected-(J2-PadP14)") (class "Default")
      (node (ref "J2") (pin "P14") (pinfunction "P14_P14") (pintype "passive+no_connect"))
    )
    (net (code "51") (name "unconnected-(U1-NC-Pad9)") (class "Default")
      (node (ref "U1") (pin "9") (pinfunction "NC_9") (pintype "input+no_connect"))
    )
    (net (code "52") (name "unconnected-(U1-NC_2-Pad6)") (class "Default")
      (node (ref "U1") (pin "6") (pinfunction "NC_2_6") (pintype "input+no_connect"))
    )
    (net (code "53") (name "unconnected-(U1-NC_3-Pad8)") (class "Default")
      (node (ref "U1") (pin "8") (pinfunction "NC_3_8") (pintype "input+no_connect"))
    )
    (net (code "54") (name "unconnected-(U2-COMP-Pad2)") (class "Default")
      (node (ref "U2") (pin "2") (pinfunction "COMP_2") (pintype "output+no_connect"))
    )
    (net (code "55") (name "unconnected-(U2-RMID-Pad7)") (class "Default")
      (node (ref "U2") (pin "7") (pinfunction "RMID_7") (pintype "passive+no_connect"))
    )
    (net (code "56") (name "unconnected-(U2-RTOP-Pad4)") (class "Default")
      (node (ref "U2") (pin "4") (pinfunction "RTOP_4") (pintype "passive+no_connect"))
    )
  )
)
